# CarrierConnector.net
KiCad netlist of a schematic drawn in Altium Designer
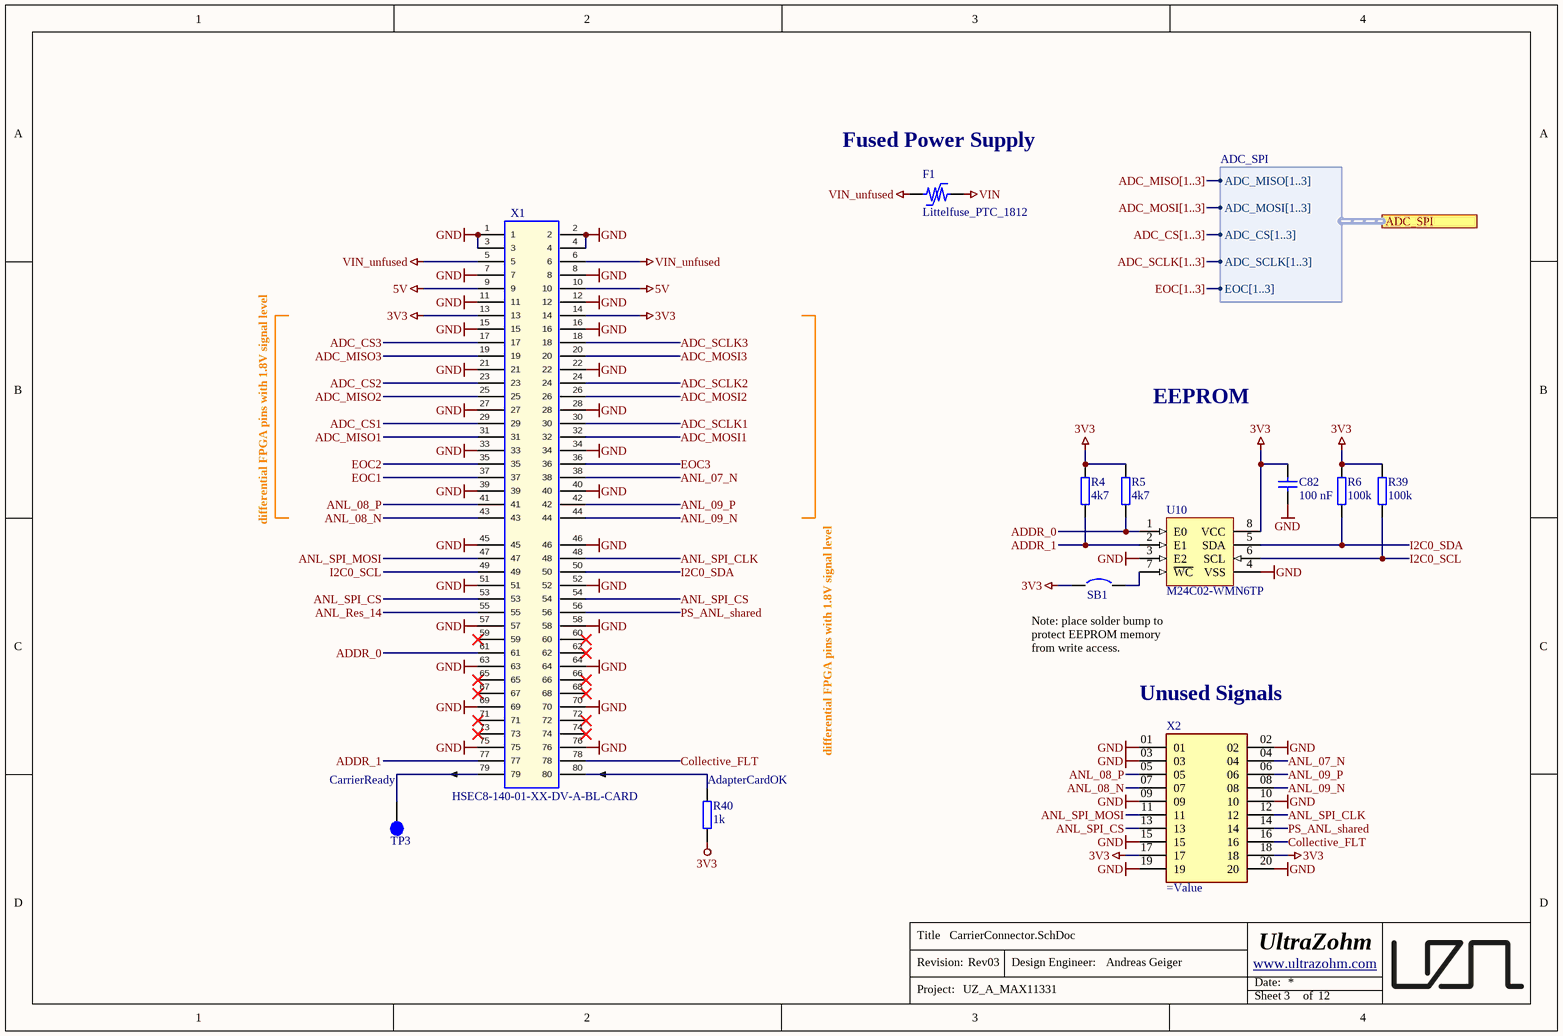
[diagram p0: CarrierConnector.SchDoc]

(export (version "E")
  (design (tool "Eeschema 10.0.6"))
  (components
    (comp (ref "C82")
      (value "100 nF")
      (footprint "C_0603_TE")
      (description "Generic capacitor")
      (fields
        (field (name "MANUFACTURER PART NUMBER") "UZgen_C_0603_100nF_50V_X7R")
        (field (name "MANUFACTURER") "UZgen")
        (field (name "CREATED FROM") "AGeiger")
      )
      (libsource (lib "user") (part "CAP-NP"))
    )
    (comp (ref "F1")
      (value "Littelfuse_PTC_1812")
      (footprint "1812_PTC_Polyfuse_Littelfuse")
      (description "POLYSWITCH RESETTABLE DEVICES")
      (fields
        (field (name "MPN") "miniASMDC110F/24")
        (field (name "MF") "Littelfuse")
        (field (name "CREATED") "2019_02_10_AGeiger")
        (field (name "CREATED FROM") "MHlatky")
      )
      (libsource (lib "user") (part "Littelfuse_PTC_1812"))
    )
    (comp (ref "R4")
      (value "4k7")
      (footprint "R_0603_TE")
      (description "Generic resistor")
      (fields
        (field (name "MANUFACTURER PART NUMBER") "UZgen_R_0603_4k7")
        (field (name "MANUFACTURER") "UZgen")
        (field (name "CREATED FROM") "UZgenTool")
      )
      (libsource (lib "user") (part "RES"))
    )
    (comp (ref "R5")
      (value "4k7")
      (footprint "R_0603_TE")
      (description "Generic resistor")
      (fields
        (field (name "MANUFACTURER PART NUMBER") "UZgen_R_0603_4k7")
        (field (name "MANUFACTURER") "UZgen")
        (field (name "CREATED FROM") "UZgenTool")
      )
      (libsource (lib "user") (part "RES"))
    )
    (comp (ref "R6")
      (value "100k")
      (footprint "R_0603_TE")
      (description "Generic resistor")
      (fields
        (field (name "MANUFACTURER PART NUMBER") "UZgen_R_0603_100k")
        (field (name "MANUFACTURER") "UZgen")
        (field (name "CREATED FROM") "UZgenTool")
      )
      (libsource (lib "user") (part "RES"))
    )
    (comp (ref "R39")
      (value "100k")
      (footprint "R_0603_TE")
      (description "Generic resistor")
      (fields
        (field (name "MANUFACTURER PART NUMBER") "UZgen_R_0603_100k")
        (field (name "MANUFACTURER") "UZgen")
        (field (name "CREATED FROM") "UZgenTool")
      )
      (libsource (lib "user") (part "RES"))
    )
    (comp (ref "R40")
      (value "1k")
      (footprint "R_0603_TE")
      (description "Generic resistor")
      (fields
        (field (name "MANUFACTURER PART NUMBER") "UZgen_R_0603_1k")
        (field (name "MANUFACTURER") "UZgen")
        (field (name "CREATED FROM") "UZgenTool")
      )
      (libsource (lib "user") (part "RES"))
    )
    (comp (ref "SB1")
      (value "Solder Bump 0603")
      (footprint "SB_0603")
      (fields (field (name "CREATED FROM") "AGeiger"))
      (libsource (lib "user") (part "Solder_Bump"))
    )
    (comp (ref "TP3")
      (value "Testpoint 1mm")
      (footprint "TP_1mm")
      (fields
        (field (name "MANUFACTURER PART NUMBER") "Testpoint_1mm")
        (field (name "MANUFACTURER") "UltraZohm")
        (field (name "CREATED") "2018_06_25_AGeiger")
        (field (name "CREATED FROM") "AGeiger")
      )
      (libsource (lib "user") (part "TP_1mm"))
    )
    (comp (ref "U10")
      (value "M24C02-WMN6TP")
      (footprint "D0008A_N")
      (description "2Kbit I2C SOP-8 EEPROM ROHS")
      (fields
        (field (name "MANUFACTURER") "STMicroelectronics")
        (field (name "LCSC PART NUMBER") "C7562")
        (field (name "CREATED FROM") "AGeiger")
      )
      (libsource (lib "user") (part "M24256"))
    )
    (comp (ref "X1")
      (value "HSEC8-140-01-XX-DV-A-BL-CARD")
      (footprint "HSEC8-140-01-XX-DV-A-BL-CARD")
      (description "Mating Card Layout for HSEC8-140-01-XX-DV-A-BL-CARD")
      (fields
        (field (name "MANUFACTURER") "SAMTEC")
        (field (name "CREATED") "2018_04_23_AGeiger")
        (field (name "CREATED FROM") "MHlatky")
      )
      (libsource (lib "user") (part "HSEC8-140-01-XX-DV-A-BL-CARD"))
    )
    (comp (ref "X2")
      (value "~")
      (footprint "SAMTEC_FTSH-110-X-X-DV")
      (description "Headers & Wire Housings High Reliability Header Strips, 0.050 pitch")
      (fields
        (field (name "MP") "FTSH-110-X-X-DV")
        (field (name "MANUFACTURER") "SAMTEC")
        (field (name "CREATED FROM") "AGeiger")
      )
      (libsource (lib "user") (part "FTSH-110-X-X-DV"))
    )
  )
  (nets
    (net (code "2") (name "/ADC_CS1") (class "Default")
      (node (ref "X1") (pin "29") (pinfunction "29_29") (pintype "passive"))
    )
    (net (code "3") (name "/ADC_CS2") (class "Default")
      (node (ref "X1") (pin "23") (pinfunction "23_23") (pintype "passive"))
    )
    (net (code "4") (name "/ADC_CS3") (class "Default")
      (node (ref "X1") (pin "17") (pinfunction "17_17") (pintype "passive"))
    )
    (net (code "6") (name "/ADC_MISO1") (class "Default")
      (node (ref "X1") (pin "31") (pinfunction "31_31") (pintype "passive"))
    )
    (net (code "7") (name "/ADC_MISO2") (class "Default")
      (node (ref "X1") (pin "25") (pinfunction "25_25") (pintype "passive"))
    )
    (net (code "8") (name "/ADC_MISO3") (class "Default")
      (node (ref "X1") (pin "19") (pinfunction "19_19") (pintype "passive"))
    )
    (net (code "10") (name "/ADC_MOSI1") (class "Default")
      (node (ref "X1") (pin "32") (pinfunction "32_32") (pintype "passive"))
    )
    (net (code "11") (name "/ADC_MOSI2") (class "Default")
      (node (ref "X1") (pin "26") (pinfunction "26_26") (pintype "passive"))
    )
    (net (code "12") (name "/ADC_MOSI3") (class "Default")
      (node (ref "X1") (pin "20") (pinfunction "20_20") (pintype "passive"))
    )
    (net (code "14") (name "/ADC_SCLK1") (class "Default")
      (node (ref "X1") (pin "30") (pinfunction "30_30") (pintype "passive"))
    )
    (net (code "15") (name "/ADC_SCLK2") (class "Default")
      (node (ref "X1") (pin "24") (pinfunction "24_24") (pintype "passive"))
    )
    (net (code "16") (name "/ADC_SCLK3") (class "Default")
      (node (ref "X1") (pin "18") (pinfunction "18_18") (pintype "passive"))
    )
    (net (code "18") (name "/ADDR_0") (class "Default")
      (node (ref "R5") (pin "1") (pinfunction "1_1") (pintype "passive"))
      (node (ref "U10") (pin "1") (pinfunction "E0_1") (pintype "input"))
      (node (ref "X1") (pin "61") (pinfunction "61_61") (pintype "passive"))
    )
    (net (code "19") (name "/ADDR_1") (class "Default")
      (node (ref "R4") (pin "1") (pinfunction "1_1") (pintype "passive"))
      (node (ref "U10") (pin "2") (pinfunction "E1_2") (pintype "input"))
      (node (ref "X1") (pin "77") (pinfunction "77_77") (pintype "passive"))
    )
    (net (code "20") (name "/ANL_07_N") (class "Default")
      (node (ref "X1") (pin "38") (pinfunction "38_38") (pintype "passive"))
      (node (ref "X2") (pin "04") (pinfunction "04_04") (pintype "passive"))
    )
    (net (code "21") (name "/ANL_08_N") (class "Default")
      (node (ref "X1") (pin "43") (pinfunction "43_43") (pintype "passive"))
      (node (ref "X2") (pin "07") (pinfunction "07_07") (pintype "passive"))
    )
    (net (code "22") (name "/ANL_08_P") (class "Default")
      (node (ref "X1") (pin "41") (pinfunction "41_41") (pintype "passive"))
      (node (ref "X2") (pin "05") (pinfunction "05_05") (pintype "passive"))
    )
    (net (code "23") (name "/ANL_09_N") (class "Default")
      (node (ref "X1") (pin "44") (pinfunction "44_44") (pintype "passive"))
      (node (ref "X2") (pin "08") (pinfunction "08_08") (pintype "passive"))
    )
    (net (code "24") (name "/ANL_09_P") (class "Default")
      (node (ref "X1") (pin "42") (pinfunction "42_42") (pintype "passive"))
      (node (ref "X2") (pin "06") (pinfunction "06_06") (pintype "passive"))
    )
    (net (code "25") (name "/ANL_Res_14") (class "Default")
      (node (ref "X1") (pin "55") (pinfunction "55_55") (pintype "passive"))
    )
    (net (code "26") (name "/ANL_SPI_CLK") (class "Default")
      (node (ref "X1") (pin "48") (pinfunction "48_48") (pintype "passive"))
      (node (ref "X2") (pin "12") (pinfunction "12_12") (pintype "passive"))
    )
    (net (code "27") (name "/ANL_SPI_CS") (class "Default")
      (node (ref "X1") (pin "53") (pinfunction "53_53") (pintype "passive"))
      (node (ref "X1") (pin "54") (pinfunction "54_54") (pintype "passive"))
      (node (ref "X2") (pin "13") (pinfunction "13_13") (pintype "passive"))
    )
    (net (code "28") (name "/ANL_SPI_MOSI") (class "Default")
      (node (ref "X1") (pin "47") (pinfunction "47_47") (pintype "passive"))
      (node (ref "X2") (pin "11") (pinfunction "11_11") (pintype "passive"))
    )
    (net (code "29") (name "/Collective_FLT") (class "Default")
      (node (ref "X1") (pin "78") (pinfunction "78_78") (pintype "passive"))
      (node (ref "X2") (pin "16") (pinfunction "16_16") (pintype "passive"))
    )
    (net (code "30") (name "/EOC1") (class "Default")
      (node (ref "X1") (pin "37") (pinfunction "37_37") (pintype "passive"))
    )
    (net (code "31") (name "/EOC2") (class "Default")
      (node (ref "X1") (pin "35") (pinfunction "35_35") (pintype "passive"))
    )
    (net (code "32") (name "/EOC3") (class "Default")
      (node (ref "X1") (pin "36") (pinfunction "36_36") (pintype "passive"))
    )
    (net (code "34") (name "/I2C0_SCL") (class "Default")
      (node (ref "R39") (pin "1") (pinfunction "1_1") (pintype "passive"))
      (node (ref "U10") (pin "6") (pinfunction "SCL_6") (pintype "input"))
      (node (ref "X1") (pin "49") (pinfunction "49_49") (pintype "passive"))
    )
    (net (code "35") (name "/I2C0_SDA") (class "Default")
      (node (ref "R6") (pin "1") (pinfunction "1_1") (pintype "passive"))
      (node (ref "U10") (pin "5") (pinfunction "SDA_5") (pintype "open_collector"))
      (node (ref "X1") (pin "50") (pinfunction "50_50") (pintype "passive"))
    )
    (net (code "36") (name "/PS_ANL_shared") (class "Default")
      (node (ref "X1") (pin "56") (pinfunction "56_56") (pintype "passive"))
      (node (ref "X2") (pin "14") (pinfunction "14_14") (pintype "passive"))
    )
    (net (code "38") (name "3V3") (class "Default")
      (node (ref "C82") (pin "1") (pinfunction "1_1") (pintype "passive"))
      (node (ref "R39") (pin "2") (pinfunction "2_2") (pintype "passive"))
      (node (ref "R4") (pin "2") (pinfunction "2_2") (pintype "passive"))
      (node (ref "R40") (pin "1") (pinfunction "1_1") (pintype "passive"))
      (node (ref "R5") (pin "2") (pinfunction "2_2") (pintype "passive"))
      (node (ref "R6") (pin "2") (pinfunction "2_2") (pintype "passive"))
      (node (ref "SB1") (pin "1") (pinfunction "1_1") (pintype "passive"))
      (node (ref "U10") (pin "8") (pinfunction "VCC_8") (pintype "power_in"))
      (node (ref "X1") (pin "13") (pinfunction "13_13") (pintype "passive"))
      (node (ref "X1") (pin "14") (pinfunction "14_14") (pintype "passive"))
      (node (ref "X2") (pin "17") (pinfunction "17_17") (pintype "passive"))
      (node (ref "X2") (pin "18") (pinfunction "18_18") (pintype "passive"))
    )
    (net (code "39") (name "5V") (class "Default")
      (node (ref "X1") (pin "10") (pinfunction "10_10") (pintype "passive"))
      (node (ref "X1") (pin "9") (pinfunction "9_9") (pintype "passive"))
    )
    (net (code "40") (name "GND") (class "Default")
      (node (ref "C82") (pin "2") (pinfunction "2_2") (pintype "passive"))
      (node (ref "U10") (pin "3") (pinfunction "E2_3") (pintype "input"))
      (node (ref "U10") (pin "4") (pinfunction "VSS_4") (pintype "power_in"))
      (node (ref "X1") (pin "1") (pinfunction "1_1") (pintype "passive"))
      (node (ref "X1") (pin "11") (pinfunction "11_11") (pintype "passive"))
      (node (ref "X1") (pin "12") (pinfunction "12_12") (pintype "passive"))
      (node (ref "X1") (pin "15") (pinfunction "15_15") (pintype "passive"))
      (node (ref "X1") (pin "16") (pinfunction "16_16") (pintype "passive"))
      (node (ref "X1") (pin "2") (pinfunction "2_2") (pintype "passive"))
      (node (ref "X1") (pin "21") (pinfunction "21_21") (pintype "passive"))
      (node (ref "X1") (pin "22") (pinfunction "22_22") (pintype "passive"))
      (node (ref "X1") (pin "27") (pinfunction "27_27") (pintype "passive"))
      (node (ref "X1") (pin "28") (pinfunction "28_28") (pintype "passive"))
      (node (ref "X1") (pin "3") (pinfunction "3_3") (pintype "passive"))
      (node (ref "X1") (pin "33") (pinfunction "33_33") (pintype "passive"))
      (node (ref "X1") (pin "34") (pinfunction "34_34") (pintype "passive"))
      (node (ref "X1") (pin "39") (pinfunction "39_39") (pintype "passive"))
      (node (ref "X1") (pin "4") (pinfunction "4_4") (pintype "passive"))
      (node (ref "X1") (pin "40") (pinfunction "40_40") (pintype "passive"))
      (node (ref "X1") (pin "45") (pinfunction "45_45") (pintype "passive"))
      (node (ref "X1") (pin "46") (pinfunction "46_46") (pintype "passive"))
      (node (ref "X1") (pin "51") (pinfunction "51_51") (pintype "passive"))
      (node (ref "X1") (pin "52") (pinfunction "52_52") (pintype "passive"))
      (node (ref "X1") (pin "57") (pinfunction "57_57") (pintype "passive"))
      (node (ref "X1") (pin "58") (pinfunction "58_58") (pintype "passive"))
      (node (ref "X1") (pin "63") (pinfunction "63_63") (pintype "passive"))
      (node (ref "X1") (pin "64") (pinfunction "64_64") (pintype "passive"))
      (node (ref "X1") (pin "69") (pinfunction "69_69") (pintype "passive"))
      (node (ref "X1") (pin "7") (pinfunction "7_7") (pintype "passive"))
      (node (ref "X1") (pin "70") (pinfunction "70_70") (pintype "passive"))
      (node (ref "X1") (pin "75") (pinfunction "75_75") (pintype "passive"))
      (node (ref "X1") (pin "76") (pinfunction "76_76") (pintype "passive"))
      (node (ref "X1") (pin "8") (pinfunction "8_8") (pintype "passive"))
      (node (ref "X2") (pin "01") (pinfunction "01_01") (pintype "passive"))
      (node (ref "X2") (pin "02") (pinfunction "02_02") (pintype "passive"))
      (node (ref "X2") (pin "03") (pinfunction "03_03") (pintype "passive"))
      (node (ref "X2") (pin "09") (pinfunction "09_09") (pintype "passive"))
      (node (ref "X2") (pin "10") (pinfunction "10_10") (pintype "passive"))
      (node (ref "X2") (pin "15") (pinfunction "15_15") (pintype "passive"))
      (node (ref "X2") (pin "19") (pinfunction "19_19") (pintype "passive"))
      (node (ref "X2") (pin "20") (pinfunction "20_20") (pintype "passive"))
    )
    (net (code "41") (name "Net-(R40-Pad2)") (class "Default")
      (node (ref "R40") (pin "2") (pinfunction "2_2") (pintype "passive"))
      (node (ref "X1") (pin "80") (pinfunction "80_80") (pintype "passive"))
    )
    (net (code "42") (name "Net-(TP3-Pad1)") (class "Default")
      (node (ref "TP3") (pin "1") (pintype "passive"))
      (node (ref "X1") (pin "79") (pinfunction "79_79") (pintype "passive"))
    )
    (net (code "43") (name "Net-(U10-~{WC})") (class "Default")
      (node (ref "SB1") (pin "2") (pinfunction "2_2") (pintype "passive"))
      (node (ref "U10") (pin "7") (pinfunction "~{WC}_7") (pintype "input"))
    )
    (net (code "44") (name "VIN") (class "Default")
      (node (ref "F1") (pin "2") (pinfunction "2_2") (pintype "passive"))
    )
    (net (code "45") (name "VIN_unfused") (class "Default")
      (node (ref "F1") (pin "1") (pinfunction "1_1") (pintype "passive"))
      (node (ref "X1") (pin "5") (pinfunction "5_5") (pintype "passive"))
      (node (ref "X1") (pin "6") (pinfunction "6_6") (pintype "passive"))
    )
    (net (code "46") (name "unconnected-(X1-Pad59)") (class "Default")
      (node (ref "X1") (pin "59") (pinfunction "59_59") (pintype "passive+no_connect"))
    )
    (net (code "47") (name "unconnected-(X1-Pad60)") (class "Default")
      (node (ref "X1") (pin "60") (pinfunction "60_60") (pintype "passive+no_connect"))
    )
    (net (code "48") (name "unconnected-(X1-Pad62)") (class "Default")
      (node (ref "X1") (pin "62") (pinfunction "62_62") (pintype "passive+no_connect"))
    )
    (net (code "49") (name "unconnected-(X1-Pad65)") (class "Default")
      (node (ref "X1") (pin "65") (pinfunction "65_65") (pintype "passive+no_connect"))
    )
    (net (code "50") (name "unconnected-(X1-Pad66)") (class "Default")
      (node (ref "X1") (pin "66") (pinfunction "66_66") (pintype "passive+no_connect"))
    )
    (net (code "51") (name "unconnected-(X1-Pad67)") (class "Default")
      (node (ref "X1") (pin "67") (pinfunction "67_67") (pintype "passive+no_connect"))
    )
    (net (code "52") (name "unconnected-(X1-Pad68)") (class "Default")
      (node (ref "X1") (pin "68") (pinfunction "68_68") (pintype "passive+no_connect"))
    )
    (net (code "53") (name "unconnected-(X1-Pad71)") (class "Default")
      (node (ref "X1") (pin "71") (pinfunction "71_71") (pintype "passive+no_connect"))
    )
    (net (code "54") (name "unconnected-(X1-Pad72)") (class "Default")
      (node (ref "X1") (pin "72") (pinfunction "72_72") (pintype "passive+no_connect"))
    )
    (net (code "55") (name "unconnected-(X1-Pad73)") (class "Default")
      (node (ref "X1") (pin "73") (pinfunction "73_73") (pintype "passive+no_connect"))
    )
    (net (code "56") (name "unconnected-(X1-Pad74)") (class "Default")
      (node (ref "X1") (pin "74") (pinfunction "74_74") (pintype "passive+no_connect"))
    )
  )
)
